# Driver_Morpheus_v4_0_SENSOR_CORRENTE.net
KiCad netlist of a schematic drawn in Altium Designer
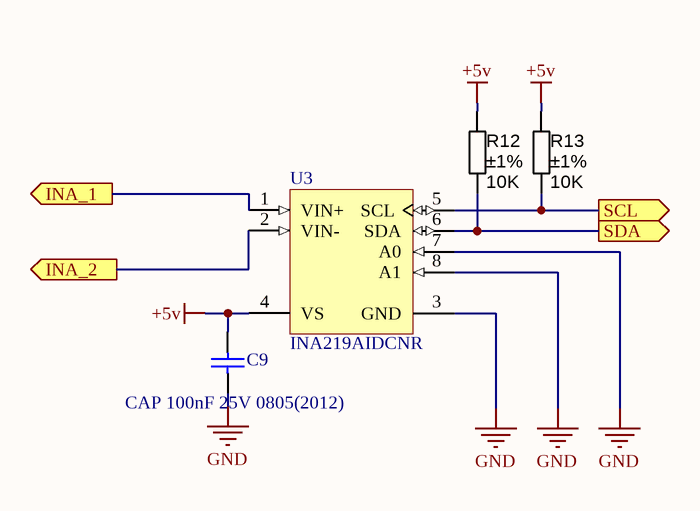
[diagram p0: Driver Morpheus v4.0 SENSOR CORRENTE.SchDoc]

(export (version "E")
  (design (tool "Eeschema 10.0.6"))
  (components
    (comp (ref "C9")
      (value "CAP 100nF 25V 0805(2012)")
      (footprint "CAPC0805(2012)145_M")
      (description "CAP 100nF 25V ±5% 0805 (2012 Metric) Thickness 1.45mm SMD")
      (fields (field (name "TOLERANCE") "Â±5%"))
      (libsource (lib "Altium Content Vault") (part "CAP"))
    )
    (comp (ref "R12")
      (value "10K")
      (footprint "RESC1608X55N")
      (description "Resistor SMD chip 10k Ohm 0.1W 1% 0603")
      (fields (field (name "TOLERANCE") "±1%") (field (name "Comment") "Thick Film"))
      (libsource (lib "PBL - Resistors") (part "RES_10K_0603_1%"))
    )
    (comp (ref "R13")
      (value "10K")
      (footprint "RESC1608X55N")
      (description "Resistor SMD chip 10k Ohm 0.1W 1% 0603")
      (fields (field (name "TOLERANCE") "±1%") (field (name "Comment") "Thick Film"))
      (libsource (lib "PBL - Resistors") (part "RES_10K_0603_1%"))
    )
    (comp (ref "U3")
      (value "INA219AIDCNR")
      (footprint "DCN0008A_M")
      (fields (field (name "MANUFACTURER") "Texas Instruments"))
      (libsource (lib "Altium Content Vault") (part "TI-INA219DCN8"))
    )
  )
  (nets
    (net (code "1") (name "+5v") (class "Default")
      (node (ref "C9") (pin "2") (pinfunction "2_2") (pintype "passive"))
      (node (ref "R12") (pin "1") (pinfunction "1_1") (pintype "passive"))
      (node (ref "R13") (pin "1") (pinfunction "1_1") (pintype "passive"))
      (node (ref "U3") (pin "4") (pinfunction "VS_4") (pintype "power_in"))
    )
    (net (code "2") (name "/INA_1") (class "Default")
      (node (ref "U3") (pin "1") (pinfunction "VIN+_1") (pintype "input"))
    )
    (net (code "3") (name "/INA_2") (class "Default")
      (node (ref "U3") (pin "2") (pinfunction "VIN-_2") (pintype "input"))
    )
    (net (code "4") (name "/SCL") (class "Default")
      (node (ref "R13") (pin "2") (pinfunction "2_2") (pintype "passive"))
      (node (ref "U3") (pin "5") (pinfunction "SCL_5") (pintype "bidirectional"))
    )
    (net (code "5") (name "/SDA") (class "Default")
      (node (ref "R12") (pin "2") (pinfunction "2_2") (pintype "passive"))
      (node (ref "U3") (pin "6") (pinfunction "SDA_6") (pintype "bidirectional"))
    )
    (net (code "6") (name "GND") (class "Default")
      (node (ref "C9") (pin "1") (pinfunction "1_1") (pintype "passive"))
      (node (ref "U3") (pin "3") (pinfunction "GND_3") (pintype "power_in"))
      (node (ref "U3") (pin "7") (pinfunction "A0_7") (pintype "input"))
      (node (ref "U3") (pin "8") (pinfunction "A1_8") (pintype "input"))
    )
  )
)
